# RightSide.net
KiCad netlist of a schematic drawn in Altium Designer
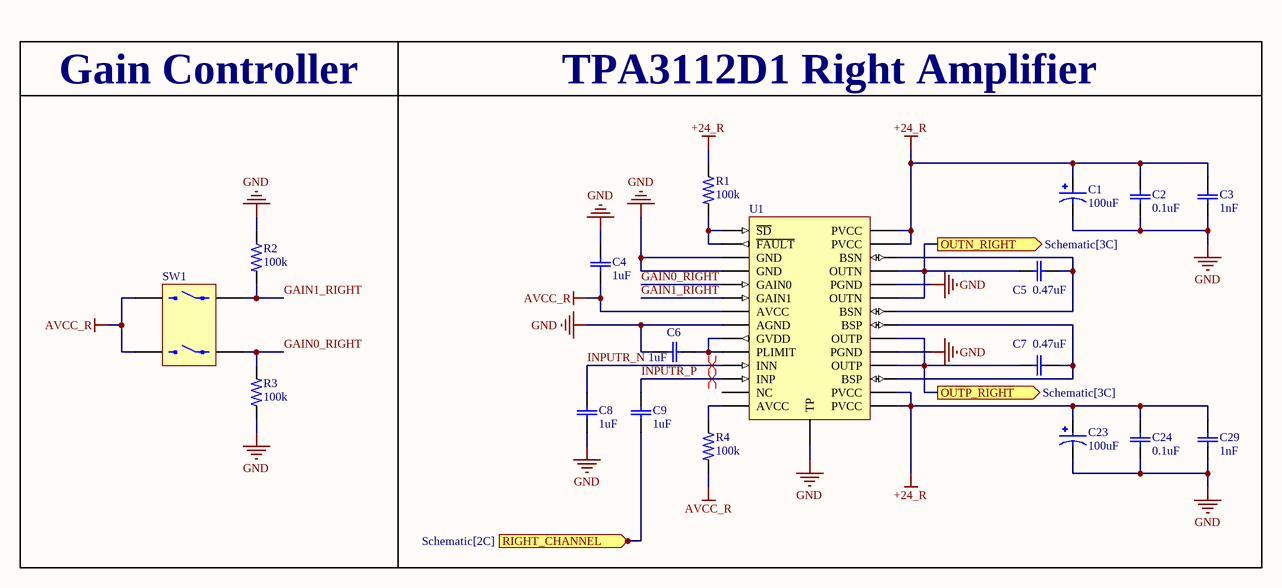
[diagram p0: RightSide.SchDoc]

(export (version "E")
  (design (tool "Eeschema 10.0.6"))
  (components
    (comp (ref "C1")
      (value "100uF")
      (footprint "CAPRADIAL_16X10")
      (fields
        (field (name "DIGI-KEY_PART_NUMBER") "P13679-ND")
        (field (name "MP") "EEU-EE2W560")
        (field (name "MF") "Panasonic")
      )
      (libsource (lib "AltiumLibrary-Mugetsu") (part "CAP ELETRO/TANT"))
    )
    (comp (ref "C2")
      (value "0.1uF")
      (footprint "CERAMIC0805")
      (fields (field (name "MF") "KEMET") (field (name "MP") "TAJC226M025RNJ"))
      (libsource (lib "AltiumLibrary-Mugetsu") (part "Cap"))
    )
    (comp (ref "C3")
      (value "1nF")
      (footprint "CERAMIC0603")
      (fields (field (name "MF") "KEMET") (field (name "MP") "TAJC226M025RNJ"))
      (libsource (lib "AltiumLibrary-Mugetsu") (part "Cap"))
    )
    (comp (ref "C4")
      (value "1uF")
      (footprint "CERAMIC0603")
      (fields (field (name "MF") "KEMET") (field (name "MP") "TAJC226M025RNJ"))
      (libsource (lib "AltiumLibrary-Mugetsu") (part "Cap"))
    )
    (comp (ref "C5")
      (value "0.47uF")
      (footprint "CERAMIC0603")
      (fields (field (name "MF") "KEMET") (field (name "MP") "TAJC226M025RNJ"))
      (libsource (lib "AltiumLibrary-Mugetsu") (part "Cap"))
    )
    (comp (ref "C6")
      (value "1uF")
      (footprint "CERAMIC0603")
      (fields (field (name "MF") "KEMET") (field (name "MP") "TAJC226M025RNJ"))
      (libsource (lib "AltiumLibrary-Mugetsu") (part "Cap"))
    )
    (comp (ref "C7")
      (value "0.47uF")
      (footprint "CERAMIC0603")
      (fields (field (name "MF") "KEMET") (field (name "MP") "TAJC226M025RNJ"))
      (libsource (lib "AltiumLibrary-Mugetsu") (part "Cap"))
    )
    (comp (ref "C8")
      (value "1uF")
      (footprint "CERAMIC0603")
      (fields (field (name "MF") "KEMET") (field (name "MP") "TAJC226M025RNJ"))
      (libsource (lib "AltiumLibrary-Mugetsu") (part "Cap"))
    )
    (comp (ref "C9")
      (value "1uF")
      (footprint "CERAMIC0603")
      (fields (field (name "MF") "KEMET") (field (name "MP") "TAJC226M025RNJ"))
      (libsource (lib "AltiumLibrary-Mugetsu") (part "Cap"))
    )
    (comp (ref "C23")
      (value "100uF")
      (footprint "CAPRADIAL_16X10")
      (fields
        (field (name "DIGI-KEY_PART_NUMBER") "P13679-ND")
        (field (name "MP") "EEU-EE2W560")
        (field (name "MF") "Panasonic")
      )
      (libsource (lib "AltiumLibrary-Mugetsu") (part "CAP ELETRO/TANT"))
    )
    (comp (ref "C24")
      (value "0.1uF")
      (footprint "CERAMIC0805")
      (fields (field (name "MF") "KEMET") (field (name "MP") "TAJC226M025RNJ"))
      (libsource (lib "AltiumLibrary-Mugetsu") (part "Cap"))
    )
    (comp (ref "C29")
      (value "1nF")
      (footprint "CERAMIC0603")
      (fields (field (name "MF") "KEMET") (field (name "MP") "TAJC226M025RNJ"))
      (libsource (lib "AltiumLibrary-Mugetsu") (part "Cap"))
    )
    (comp (ref "R1")
      (value "100k")
      (footprint "RES0603")
      (fields (field (name "MP") "3-1879460-6"))
      (libsource (lib "AltiumLibrary-Mugetsu") (part "RESISTOR SMD"))
    )
    (comp (ref "R2")
      (value "100k")
      (footprint "RES0603")
      (fields (field (name "MP") "3-1879460-6"))
      (libsource (lib "AltiumLibrary-Mugetsu") (part "RESISTOR SMD"))
    )
    (comp (ref "R3")
      (value "100k")
      (footprint "RES0603")
      (fields (field (name "MP") "3-1879460-6"))
      (libsource (lib "AltiumLibrary-Mugetsu") (part "RESISTOR SMD"))
    )
    (comp (ref "R4")
      (value "100k")
      (footprint "RES0603")
      (fields (field (name "MP") "3-1879460-6"))
      (libsource (lib "AltiumLibrary-Mugetsu") (part "RESISTOR SMD"))
    )
    (comp (ref "SW1")
      (value "DIP SWITCH - 2 POS")
      (footprint "KF1001 - 2 POS")
      (libsource (lib "AltiumLibrary-Mugetsu") (part "DIP SWITCH - 2 POS"))
    )
    (comp (ref "U1")
      (value "TPA3112D1")
      (footprint "HTSSOP-28")
      (description "25W Filter-Free Mono Class-D Audio Power Amplifier")
      (libsource (lib "AltiumLibrary-Mugetsu") (part "TPA3112D1"))
    )
  )
  (nets
    (net (code "1") (name "+24_R") (class "Default")
      (node (ref "C1") (pin "P") (pinfunction "P_P") (pintype "passive"))
      (node (ref "C2") (pin "2") (pinfunction "C2_2") (pintype "passive"))
      (node (ref "C23") (pin "P") (pinfunction "P_P") (pintype "passive"))
      (node (ref "C24") (pin "2") (pinfunction "C2_2") (pintype "passive"))
      (node (ref "C29") (pin "2") (pinfunction "C2_2") (pintype "passive"))
      (node (ref "C3") (pin "2") (pinfunction "C2_2") (pintype "passive"))
      (node (ref "R1") (pin "1") (pinfunction "1_1") (pintype "passive"))
      (node (ref "U1") (pin "15") (pinfunction "PVCC_15") (pintype "power_in"))
      (node (ref "U1") (pin "16") (pinfunction "PVCC_16") (pintype "power_in"))
      (node (ref "U1") (pin "27") (pinfunction "PVCC_27") (pintype "passive"))
      (node (ref "U1") (pin "28") (pinfunction "PVCC_28") (pintype "power_in"))
    )
    (net (code "2") (name "/GAIN0_RIGHT") (class "Default")
      (node (ref "R3") (pin "2") (pinfunction "2_2") (pintype "passive"))
      (node (ref "SW1") (pin "1") (pinfunction "1_1") (pintype "passive"))
      (node (ref "U1") (pin "5") (pinfunction "GAIN0_5") (pintype "input"))
    )
    (net (code "3") (name "/GAIN1_RIGHT") (class "Default")
      (node (ref "R2") (pin "2") (pinfunction "2_2") (pintype "passive"))
      (node (ref "SW1") (pin "4") (pinfunction "4_4") (pintype "passive"))
      (node (ref "U1") (pin "6") (pinfunction "GAIN1_6") (pintype "input"))
    )
    (net (code "4") (name "/INPUTR_N") (class "Default")
      (node (ref "C8") (pin "2") (pinfunction "C2_2") (pintype "passive"))
      (node (ref "U1") (pin "11") (pinfunction "INN_11") (pintype "input"))
    )
    (net (code "5") (name "/INPUTR_P") (class "Default")
      (node (ref "C9") (pin "2") (pinfunction "C2_2") (pintype "passive"))
      (node (ref "U1") (pin "12") (pinfunction "INP_12") (pintype "input"))
    )
    (net (code "6") (name "/OUTN_RIGHT") (class "Default")
      (node (ref "C5") (pin "2") (pinfunction "C2_2") (pintype "passive"))
      (node (ref "U1") (pin "23") (pinfunction "OUTN_23") (pintype "passive"))
      (node (ref "U1") (pin "25") (pinfunction "OUTN_25") (pintype "passive"))
    )
    (net (code "7") (name "/OUTP_RIGHT") (class "Default")
      (node (ref "C7") (pin "2") (pinfunction "C2_2") (pintype "passive"))
      (node (ref "U1") (pin "18") (pinfunction "OUTP_18") (pintype "passive"))
      (node (ref "U1") (pin "20") (pinfunction "OUTP_20") (pintype "passive"))
    )
    (net (code "8") (name "/RIGHT_CHANNEL") (class "Default")
      (node (ref "C9") (pin "1") (pinfunction "C1_1") (pintype "passive"))
    )
    (net (code "9") (name "AVCC_R") (class "Default")
      (node (ref "C4") (pin "2") (pinfunction "C2_2") (pintype "passive"))
      (node (ref "R4") (pin "2") (pinfunction "2_2") (pintype "passive"))
      (node (ref "SW1") (pin "2") (pinfunction "2_2") (pintype "passive"))
      (node (ref "SW1") (pin "3") (pinfunction "3_3") (pintype "passive"))
      (node (ref "U1") (pin "7") (pinfunction "AVCC_7") (pintype "power_in"))
    )
    (net (code "10") (name "GND") (class "Default")
      (node (ref "C1") (pin "N") (pinfunction "N_N") (pintype "passive"))
      (node (ref "C2") (pin "1") (pinfunction "C1_1") (pintype "passive"))
      (node (ref "C23") (pin "N") (pinfunction "N_N") (pintype "passive"))
      (node (ref "C24") (pin "1") (pinfunction "C1_1") (pintype "passive"))
      (node (ref "C29") (pin "1") (pinfunction "C1_1") (pintype "passive"))
      (node (ref "C3") (pin "1") (pinfunction "C1_1") (pintype "passive"))
      (node (ref "C4") (pin "1") (pinfunction "C1_1") (pintype "passive"))
      (node (ref "C6") (pin "2") (pinfunction "C2_2") (pintype "passive"))
      (node (ref "C8") (pin "1") (pinfunction "C1_1") (pintype "passive"))
      (node (ref "R2") (pin "1") (pinfunction "1_1") (pintype "passive"))
      (node (ref "R3") (pin "1") (pinfunction "1_1") (pintype "passive"))
      (node (ref "U1") (pin "19") (pinfunction "PGND_19") (pintype "power_in"))
      (node (ref "U1") (pin "24") (pinfunction "PGND_24") (pintype "power_in"))
      (node (ref "U1") (pin "29") (pinfunction "TP_29") (pintype "power_in"))
      (node (ref "U1") (pin "3") (pinfunction "GND_3") (pintype "power_in"))
      (node (ref "U1") (pin "4") (pinfunction "GND_4") (pintype "power_in"))
      (node (ref "U1") (pin "8") (pinfunction "AGND_8") (pintype "power_in"))
    )
    (net (code "11") (name "Net-(C5-C1)") (class "Default")
      (node (ref "C5") (pin "1") (pinfunction "C1_1") (pintype "passive"))
      (node (ref "U1") (pin "22") (pinfunction "BSN_22") (pintype "bidirectional"))
      (node (ref "U1") (pin "26") (pinfunction "BSN_26") (pintype "bidirectional"))
    )
    (net (code "12") (name "Net-(C6-C1)") (class "Default")
      (node (ref "C6") (pin "1") (pinfunction "C1_1") (pintype "passive"))
      (node (ref "U1") (pin "10") (pinfunction "PLIMIT_10") (pintype "passive"))
      (node (ref "U1") (pin "9") (pinfunction "GVDD_9") (pintype "output"))
    )
    (net (code "13") (name "Net-(C7-C1)") (class "Default")
      (node (ref "C7") (pin "1") (pinfunction "C1_1") (pintype "passive"))
      (node (ref "U1") (pin "17") (pinfunction "BSP_17") (pintype "bidirectional"))
      (node (ref "U1") (pin "21") (pinfunction "BSP_21") (pintype "bidirectional"))
    )
    (net (code "14") (name "Net-(R4-Pad1)") (class "Default")
      (node (ref "R4") (pin "1") (pinfunction "1_1") (pintype "passive"))
      (node (ref "U1") (pin "14") (pinfunction "AVCC_14") (pintype "power_in"))
    )
    (net (code "15") (name "Net-(U1-~{FAULT})") (class "Default")
      (node (ref "R1") (pin "2") (pinfunction "2_2") (pintype "passive"))
      (node (ref "U1") (pin "1") (pinfunction "~{SD}_1") (pintype "input"))
      (node (ref "U1") (pin "2") (pinfunction "~{FAULT}_2") (pintype "output"))
    )
    (net (code "16") (name "unconnected-(U1-NC-Pad13)") (class "Default")
      (node (ref "U1") (pin "13") (pinfunction "NC_13") (pintype "passive"))
    )
  )
)
